# ELEKTRA-PMIC_v0_2-Half_frame_shield_for_.net
KiCad netlist of a schematic drawn in EAGLE
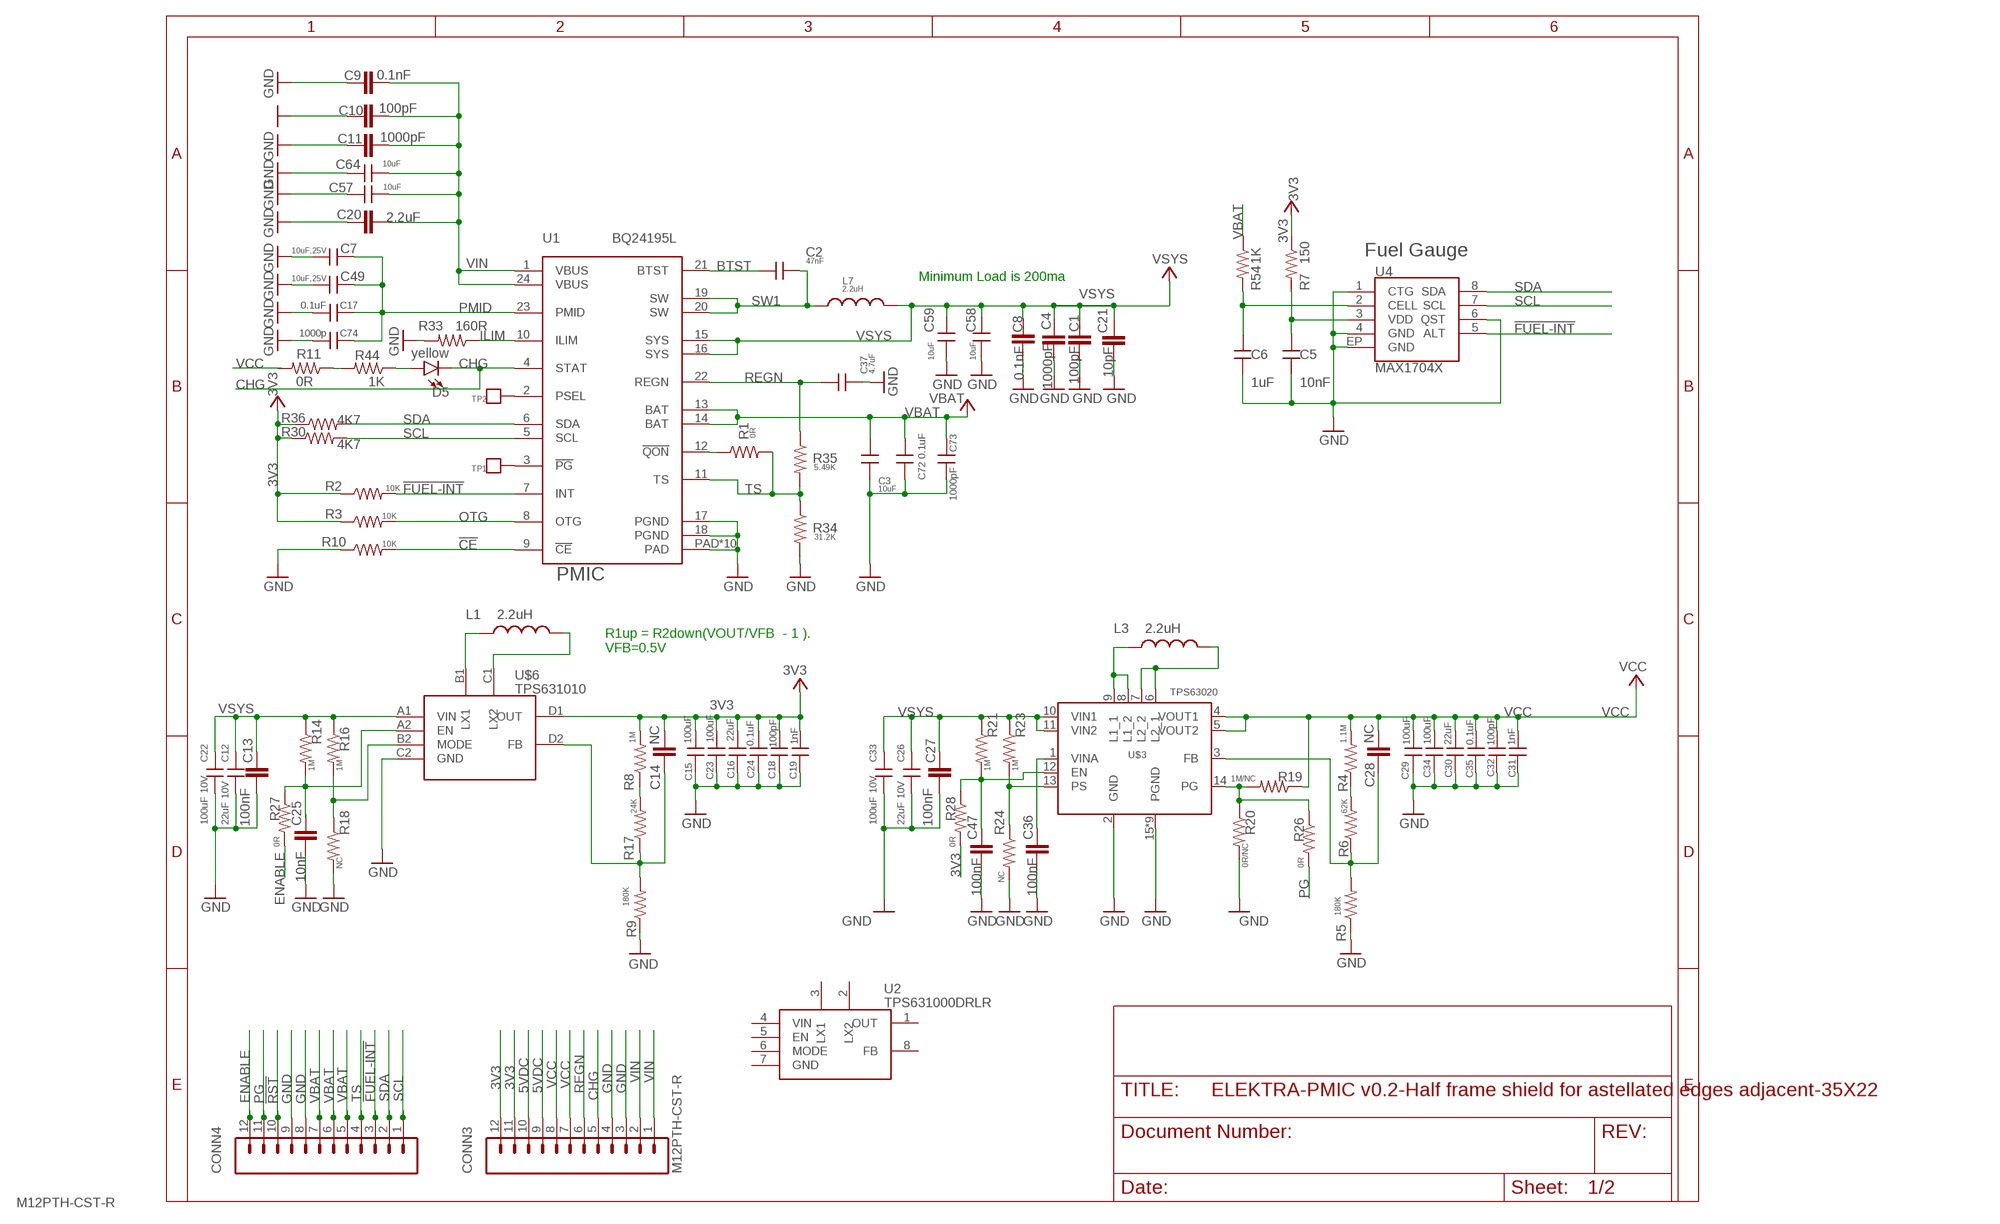
[diagram p0: schematic, sheet 1]

(export (version "E")
  (design (tool "Eeschema 10.0.6"))
  (components
    (comp (ref "C1")
      (value "100pF")
      (footprint "eagle-import:C0402_B")
      (libsource (lib "eagle-import") (part "CAP_1"))
    )
    (comp (ref "C2")
      (value "47nF")
      (footprint "eagle-import:C-0402")
      (libsource (lib "eagle-import") (part "particle SZ_CAP0402"))
    )
    (comp (ref "C3")
      (value "10uF")
      (footprint "eagle-import:C0603")
      (libsource (lib "eagle-import") (part "particle SZ_CAPC0603"))
    )
    (comp (ref "C4")
      (value "1000pF")
      (footprint "eagle-import:C0402_B")
      (libsource (lib "eagle-import") (part "CAP_1"))
    )
    (comp (ref "C5")
      (value "10nF")
      (footprint "eagle-import:C0402")
      (libsource (lib "eagle-import") (part "particle SZ_CAP0402A"))
    )
    (comp (ref "C6")
      (value "1uF")
      (footprint "eagle-import:C0402")
      (libsource (lib "eagle-import") (part "particle SZ_CAP0402A"))
    )
    (comp (ref "C7")
      (value "10uF,25V")
      (footprint "eagle-import:C-0603A")
      (libsource (lib "eagle-import") (part "particle SZ_CAP0603A"))
    )
    (comp (ref "C8")
      (value "0.1nF")
      (footprint "eagle-import:C0402_B")
      (libsource (lib "eagle-import") (part "CAP_1"))
    )
    (comp (ref "C9")
      (value "0.1nF")
      (footprint "eagle-import:C0402_B")
      (libsource (lib "eagle-import") (part "CAP_1"))
    )
    (comp (ref "C10")
      (value "100pF")
      (footprint "eagle-import:C0402_B")
      (libsource (lib "eagle-import") (part "CAP_1"))
    )
    (comp (ref "C11")
      (value "1000pF")
      (footprint "eagle-import:C0402_B")
      (libsource (lib "eagle-import") (part "CAP_1"))
    )
    (comp (ref "C12")
      (value "22uF 10V")
      (footprint "eagle-import:C0805")
      (libsource (lib "eagle-import") (part "particle SZ_21650216_CAPC0805"))
    )
    (comp (ref "C13")
      (value "100nF")
      (footprint "eagle-import:C0402_B")
      (libsource (lib "eagle-import") (part "CAP_1"))
    )
    (comp (ref "C14")
      (value "NC")
      (footprint "eagle-import:C0402_B")
      (libsource (lib "eagle-import") (part "CAP_1"))
    )
    (comp (ref "C15")
      (value "100uF")
      (footprint "eagle-import:C1206")
      (libsource (lib "eagle-import") (part "particle SZ_21650216_CAPC1206"))
    )
    (comp (ref "C16")
      (value "22uF")
      (footprint "eagle-import:C-0603A")
      (libsource (lib "eagle-import") (part "particle SZ_21650216_CAP0603A"))
    )
    (comp (ref "C17")
      (value "0.1uF")
      (footprint "eagle-import:C0402")
      (libsource (lib "eagle-import") (part "CAP0402A"))
    )
    (comp (ref "C18")
      (value "100pF")
      (footprint "eagle-import:C0402")
      (libsource (lib "eagle-import") (part "particle SZ_CAP0402A"))
    )
    (comp (ref "C19")
      (value "1nF")
      (footprint "eagle-import:C0402")
      (libsource (lib "eagle-import") (part "particle SZ_CAP0402A"))
    )
    (comp (ref "C20")
      (value "2.2uF")
      (footprint "eagle-import:C0402_B")
      (libsource (lib "eagle-import") (part "CAP_1"))
    )
    (comp (ref "C21")
      (value "10pF")
      (footprint "eagle-import:C0402_B")
      (libsource (lib "eagle-import") (part "CAP_1"))
    )
    (comp (ref "C22")
      (value "100uF 10V")
      (footprint "eagle-import:C1206")
      (libsource (lib "eagle-import") (part "particle SZ_21650216_CAPC1206"))
    )
    (comp (ref "C23")
      (value "100uF")
      (footprint "eagle-import:C1206")
      (libsource (lib "eagle-import") (part "particle SZ_21650216_CAPC1206"))
    )
    (comp (ref "C24")
      (value "0.1uF")
      (footprint "eagle-import:C0402")
      (libsource (lib "eagle-import") (part "particle SZ_CAP0402A"))
    )
    (comp (ref "C25")
      (value "10nF")
      (footprint "eagle-import:C0402_B")
      (libsource (lib "eagle-import") (part "CAP_1"))
    )
    (comp (ref "C26")
      (value "22uF 10V")
      (footprint "eagle-import:C0805")
      (libsource (lib "eagle-import") (part "particle SZ_21650216_CAPC0805"))
    )
    (comp (ref "C27")
      (value "100nF")
      (footprint "eagle-import:C0402_B")
      (libsource (lib "eagle-import") (part "CAP_1"))
    )
    (comp (ref "C28")
      (value "NC")
      (footprint "eagle-import:C0402_B")
      (libsource (lib "eagle-import") (part "CAP_1"))
    )
    (comp (ref "C29")
      (value "100uF")
      (footprint "eagle-import:C1206")
      (libsource (lib "eagle-import") (part "particle SZ_21650216_CAPC1206"))
    )
    (comp (ref "C30")
      (value "22uF")
      (footprint "eagle-import:C-0603A")
      (libsource (lib "eagle-import") (part "particle SZ_21650216_CAP0603A"))
    )
    (comp (ref "C31")
      (value "1nF")
      (footprint "eagle-import:C0402")
      (libsource (lib "eagle-import") (part "particle SZ_CAP0402A"))
    )
    (comp (ref "C32")
      (value "100pF")
      (footprint "eagle-import:C0402")
      (libsource (lib "eagle-import") (part "particle SZ_CAP0402A"))
    )
    (comp (ref "C33")
      (value "100uF 10V")
      (footprint "eagle-import:C1206")
      (libsource (lib "eagle-import") (part "particle SZ_21650216_CAPC1206"))
    )
    (comp (ref "C34")
      (value "100uF")
      (footprint "eagle-import:C1206")
      (libsource (lib "eagle-import") (part "particle SZ_21650216_CAPC1206"))
    )
    (comp (ref "C35")
      (value "0.1uF")
      (footprint "eagle-import:C0402")
      (libsource (lib "eagle-import") (part "particle SZ_CAP0402A"))
    )
    (comp (ref "C36")
      (value "100nF")
      (footprint "eagle-import:C0402_B")
      (libsource (lib "eagle-import") (part "CAP_1"))
    )
    (comp (ref "C37")
      (value "4.7uF")
      (footprint "eagle-import:C0402")
      (libsource (lib "eagle-import") (part "particle SZ_CAP0402A"))
    )
    (comp (ref "C47")
      (value "100nF")
      (footprint "eagle-import:C0402_B")
      (libsource (lib "eagle-import") (part "CAP_1"))
    )
    (comp (ref "C49")
      (value "10uF,25V")
      (footprint "eagle-import:C-0603A")
      (libsource (lib "eagle-import") (part "particle SZ_CAP0603A"))
    )
    (comp (ref "C57")
      (value "10uF")
      (footprint "eagle-import:C-0603A")
      (libsource (lib "eagle-import") (part "particle SZ_CAP0603A"))
    )
    (comp (ref "C58")
      (value "10uF")
      (footprint "eagle-import:C-0603A")
      (libsource (lib "eagle-import") (part "particle SZ_CAP0603A"))
    )
    (comp (ref "C59")
      (value "10uF")
      (footprint "eagle-import:C-0603A")
      (libsource (lib "eagle-import") (part "particle SZ_CAP0603A"))
    )
    (comp (ref "C64")
      (value "10uF")
      (footprint "eagle-import:C-0603A")
      (libsource (lib "eagle-import") (part "particle SZ_CAP0603A"))
    )
    (comp (ref "C72")
      (value "0.1uF")
      (footprint "eagle-import:C-0402")
      (libsource (lib "eagle-import") (part "particle SZ_CAP0402"))
    )
    (comp (ref "C73")
      (value "1000pF")
      (footprint "eagle-import:C-0402")
      (libsource (lib "eagle-import") (part "particle SZ_CAP0402"))
    )
    (comp (ref "C74")
      (value "1000p")
      (footprint "eagle-import:C-0402")
      (libsource (lib "eagle-import") (part "particle SZ_CAP0402"))
    )
    (comp (ref "CONN3")
      (value "M12PTH-CST-R")
      (footprint "eagle-import:1X12-CASTELLATED")
      (libsource (lib "eagle-import") (part "M12PTH-CST-R"))
    )
    (comp (ref "CONN4")
      (value "M12PTH-CST-R")
      (footprint "eagle-import:1X12-CASTELLATED")
      (libsource (lib "eagle-import") (part "M12PTH-CST-R"))
    )
    (comp (ref "D5")
      (value "yellow")
      (footprint "eagle-import:LED-0603")
      (libsource (lib "eagle-import") (part "LED-RED0603"))
    )
    (comp (ref "L1")
      (value "2.2uH")
      (footprint "eagle-import:INDUCTOR-VLS-E")
      (libsource (lib "eagle-import") (part "INDUCTOR-SPARKFUNVLS3012ET-4R7M"))
    )
    (comp (ref "L3")
      (value "2.2uH")
      (footprint "eagle-import:INDUCTOR-VLS-E")
      (libsource (lib "eagle-import") (part "INDUCTOR-SPARKFUNVLS3012ET-4R7M"))
    )
    (comp (ref "L7")
      (value "2.2uH")
      (footprint "eagle-import:INDUCTOR-4040")
      (libsource (lib "eagle-import") (part "INDUCTORI"))
    )
    (comp (ref "R1")
      (value "0R")
      (footprint "eagle-import:R0402_B")
      (libsource (lib "eagle-import") (part "Spark_R-US_"))
    )
    (comp (ref "R2")
      (value "10K")
      (footprint "eagle-import:R0402_B")
      (libsource (lib "eagle-import") (part "Spark_R-US_"))
    )
    (comp (ref "R3")
      (value "10K")
      (footprint "eagle-import:R0402_B")
      (libsource (lib "eagle-import") (part "Spark_R-US_"))
    )
    (comp (ref "R4")
      (value "1.1M")
      (footprint "eagle-import:R0402_B")
      (libsource (lib "eagle-import") (part "Spark_R-US_"))
    )
    (comp (ref "R5")
      (value "180K")
      (footprint "eagle-import:R0402_B")
      (libsource (lib "eagle-import") (part "Spark_R-US_"))
    )
    (comp (ref "R6")
      (value "62K")
      (footprint "eagle-import:R0402_B")
      (libsource (lib "eagle-import") (part "Spark_R-US_"))
    )
    (comp (ref "R7")
      (value "150")
      (footprint "eagle-import:R0402_B")
      (libsource (lib "eagle-import") (part "R-US_"))
    )
    (comp (ref "R8")
      (value "1M")
      (footprint "eagle-import:R0402_B")
      (libsource (lib "eagle-import") (part "Spark_R-US_"))
    )
    (comp (ref "R9")
      (value "180K")
      (footprint "eagle-import:R0402_B")
      (libsource (lib "eagle-import") (part "Spark_R-US_"))
    )
    (comp (ref "R10")
      (value "10K")
      (footprint "eagle-import:R0402_B")
      (libsource (lib "eagle-import") (part "Spark_R-US_"))
    )
    (comp (ref "R11")
      (value "0R")
      (footprint "eagle-import:R0402_B")
      (libsource (lib "eagle-import") (part "R-US_"))
    )
    (comp (ref "R14")
      (value "1M")
      (footprint "eagle-import:R0402_B")
      (libsource (lib "eagle-import") (part "Spark_R-US_"))
    )
    (comp (ref "R16")
      (value "1M")
      (footprint "eagle-import:R0402_B")
      (libsource (lib "eagle-import") (part "Spark_R-US_"))
    )
    (comp (ref "R17")
      (value "24K")
      (footprint "eagle-import:R0402_B")
      (libsource (lib "eagle-import") (part "Spark_R-US_"))
    )
    (comp (ref "R18")
      (value "NC")
      (footprint "eagle-import:R0402_B")
      (libsource (lib "eagle-import") (part "Spark_R-US_"))
    )
    (comp (ref "R19")
      (value "1M/NC")
      (footprint "eagle-import:R0402_B")
      (libsource (lib "eagle-import") (part "Spark_R-US_"))
    )
    (comp (ref "R20")
      (value "0R/NC")
      (footprint "eagle-import:R0402_B")
      (libsource (lib "eagle-import") (part "Spark_R-US_"))
    )
    (comp (ref "R21")
      (value "1M")
      (footprint "eagle-import:R0402_B")
      (libsource (lib "eagle-import") (part "Spark_R-US_"))
    )
    (comp (ref "R23")
      (value "1M")
      (footprint "eagle-import:R0402_B")
      (libsource (lib "eagle-import") (part "Spark_R-US_"))
    )
    (comp (ref "R24")
      (value "NC")
      (footprint "eagle-import:R0402_B")
      (libsource (lib "eagle-import") (part "Spark_R-US_"))
    )
    (comp (ref "R26")
      (value "0R")
      (footprint "eagle-import:R0402_B")
      (libsource (lib "eagle-import") (part "Spark_R-US_"))
    )
    (comp (ref "R27")
      (value "0R")
      (footprint "eagle-import:R0402_B")
      (libsource (lib "eagle-import") (part "Spark_R-US_"))
    )
    (comp (ref "R28")
      (value "0R")
      (footprint "eagle-import:R0402_B")
      (libsource (lib "eagle-import") (part "Spark_R-US_"))
    )
    (comp (ref "R30")
      (value "4K7")
      (footprint "eagle-import:R0402_B")
      (libsource (lib "eagle-import") (part "R-US_"))
    )
    (comp (ref "R33")
      (value "160R")
      (footprint "eagle-import:R0402_B")
      (libsource (lib "eagle-import") (part "R-US_"))
    )
    (comp (ref "R34")
      (value "31.2K")
      (footprint "eagle-import:R0402_B")
      (libsource (lib "eagle-import") (part "Spark_R-US_"))
    )
    (comp (ref "R35")
      (value "5.49K")
      (footprint "eagle-import:R0402_B")
      (libsource (lib "eagle-import") (part "Spark_R-US_"))
    )
    (comp (ref "R36")
      (value "4K7")
      (footprint "eagle-import:R0402_B")
      (libsource (lib "eagle-import") (part "R-US_"))
    )
    (comp (ref "R44")
      (value "1K")
      (footprint "eagle-import:R0402_B")
      (libsource (lib "eagle-import") (part "R-US_"))
    )
    (comp (ref "R54")
      (value "1K")
      (footprint "eagle-import:R0402_B")
      (libsource (lib "eagle-import") (part "R-US_"))
    )
    (comp (ref "TP1")
      (value "TP")
      (footprint "eagle-import:TP0.7MM")
      (libsource (lib "eagle-import") (part "TP"))
    )
    (comp (ref "TP2")
      (value "TP")
      (footprint "eagle-import:TP0.7MM")
      (libsource (lib "eagle-import") (part "TP"))
    )
    (comp (ref "U$3")
      (value "TPS63020")
      (footprint "eagle-import:TPS63020")
      (libsource (lib "eagle-import") (part "TPS63020"))
    )
    (comp (ref "U$6")
      (value "TPS631010")
      (footprint "eagle-import:DSBGA")
      (libsource (lib "eagle-import") (part "TPS631010"))
    )
    (comp (ref "U1")
      (value "BQ24195L")
      (footprint "eagle-import:QFN24")
      (libsource (lib "eagle-import") (part "BQ24298RTWR"))
    )
    (comp (ref "U2")
      (value "TPS631000DRLR")
      (footprint "eagle-import:SOT538")
      (libsource (lib "eagle-import") (part "TPS631000DRLR"))
    )
    (comp (ref "U4")
      (value "MAX1704X")
      (footprint "eagle-import:TDFN-8")
      (libsource (lib "eagle-import") (part "MAX1704X"))
    )
  )
  (nets
    (net (code "1") (name "3V3") (class "Default")
      (node (ref "C14") (pin "2") (pinfunction "P$2_2") (pintype "passive"))
      (node (ref "C15") (pin "1") (pinfunction "1_1") (pintype "bidirectional"))
      (node (ref "C16") (pin "1") (pinfunction "1_1") (pintype "bidirectional"))
      (node (ref "C18") (pin "1") (pinfunction "1_1") (pintype "bidirectional"))
      (node (ref "C19") (pin "1") (pinfunction "1_1") (pintype "bidirectional"))
      (node (ref "C23") (pin "1") (pinfunction "1_1") (pintype "bidirectional"))
      (node (ref "C24") (pin "1") (pinfunction "1_1") (pintype "bidirectional"))
      (node (ref "CONN3") (pin "11") (pinfunction "11_11") (pintype "passive"))
      (node (ref "CONN3") (pin "12") (pinfunction "12_12") (pintype "passive"))
      (node (ref "R2") (pin "1") (pinfunction "1_1") (pintype "passive"))
      (node (ref "R28") (pin "2") (pinfunction "2_2") (pintype "passive"))
      (node (ref "R3") (pin "1") (pinfunction "1_1") (pintype "passive"))
      (node (ref "R30") (pin "1") (pinfunction "1_1") (pintype "passive"))
      (node (ref "R36") (pin "1") (pinfunction "1_1") (pintype "passive"))
      (node (ref "R7") (pin "1") (pinfunction "1_1") (pintype "passive"))
      (node (ref "R8") (pin "2") (pinfunction "2_2") (pintype "passive"))
      (node (ref "U$6") (pin "D1") (pinfunction "OUT_D1") (pintype "bidirectional"))
    )
    (net (code "2") (name "5VDC") (class "Default")
      (node (ref "CONN3") (pin "10") (pinfunction "10_10") (pintype "passive"))
      (node (ref "CONN3") (pin "9") (pinfunction "9_9") (pintype "passive"))
    )
    (net (code "3") (name "BTST") (class "Default")
      (node (ref "C2") (pin "1") (pinfunction "1_1") (pintype "bidirectional"))
      (node (ref "U1") (pin "21") (pinfunction "BTST_21") (pintype "bidirectional"))
    )
    (net (code "4") (name "CHG") (class "Default")
      (node (ref "CONN3") (pin "5") (pinfunction "5_5") (pintype "passive"))
      (node (ref "D5") (pin "C") (pinfunction "C_C") (pintype "passive"))
      (node (ref "U1") (pin "4") (pinfunction "STAT_4") (pintype "bidirectional"))
    )
    (net (code "5") (name "ENABLE") (class "Default")
      (node (ref "CONN4") (pin "12") (pinfunction "12_12") (pintype "passive"))
      (node (ref "R27") (pin "2") (pinfunction "2_2") (pintype "passive"))
    )
    (net (code "6") (name "GND") (class "Default")
      (node (ref "C1") (pin "1") (pinfunction "P$1_1") (pintype "passive"))
      (node (ref "C10") (pin "1") (pinfunction "P$1_1") (pintype "passive"))
      (node (ref "C11") (pin "1") (pinfunction "P$1_1") (pintype "passive"))
      (node (ref "C12") (pin "2") (pinfunction "2_2") (pintype "bidirectional"))
      (node (ref "C13") (pin "1") (pinfunction "P$1_1") (pintype "passive"))
      (node (ref "C15") (pin "2") (pinfunction "2_2") (pintype "bidirectional"))
      (node (ref "C16") (pin "2") (pinfunction "2_2") (pintype "bidirectional"))
      (node (ref "C17") (pin "1") (pinfunction "1_1") (pintype "bidirectional"))
      (node (ref "C18") (pin "2") (pinfunction "2_2") (pintype "bidirectional"))
      (node (ref "C19") (pin "2") (pinfunction "2_2") (pintype "bidirectional"))
      (node (ref "C20") (pin "1") (pinfunction "P$1_1") (pintype "passive"))
      (node (ref "C21") (pin "1") (pinfunction "P$1_1") (pintype "passive"))
      (node (ref "C22") (pin "2") (pinfunction "2_2") (pintype "bidirectional"))
      (node (ref "C23") (pin "2") (pinfunction "2_2") (pintype "bidirectional"))
      (node (ref "C24") (pin "2") (pinfunction "2_2") (pintype "bidirectional"))
      (node (ref "C25") (pin "1") (pinfunction "P$1_1") (pintype "passive"))
      (node (ref "C26") (pin "2") (pinfunction "2_2") (pintype "bidirectional"))
      (node (ref "C27") (pin "1") (pinfunction "P$1_1") (pintype "passive"))
      (node (ref "C29") (pin "2") (pinfunction "2_2") (pintype "bidirectional"))
      (node (ref "C3") (pin "2") (pinfunction "2_2") (pintype "bidirectional"))
      (node (ref "C30") (pin "2") (pinfunction "2_2") (pintype "bidirectional"))
      (node (ref "C31") (pin "2") (pinfunction "2_2") (pintype "bidirectional"))
      (node (ref "C32") (pin "2") (pinfunction "2_2") (pintype "bidirectional"))
      (node (ref "C33") (pin "2") (pinfunction "2_2") (pintype "bidirectional"))
      (node (ref "C34") (pin "2") (pinfunction "2_2") (pintype "bidirectional"))
      (node (ref "C35") (pin "2") (pinfunction "2_2") (pintype "bidirectional"))
      (node (ref "C36") (pin "1") (pinfunction "P$1_1") (pintype "passive"))
      (node (ref "C37") (pin "2") (pinfunction "2_2") (pintype "bidirectional"))
      (node (ref "C4") (pin "1") (pinfunction "P$1_1") (pintype "passive"))
      (node (ref "C47") (pin "1") (pinfunction "P$1_1") (pintype "passive"))
      (node (ref "C49") (pin "2") (pinfunction "2_2") (pintype "bidirectional"))
      (node (ref "C5") (pin "2") (pinfunction "2_2") (pintype "bidirectional"))
      (node (ref "C57") (pin "2") (pinfunction "2_2") (pintype "bidirectional"))
      (node (ref "C58") (pin "2") (pinfunction "2_2") (pintype "bidirectional"))
      (node (ref "C59") (pin "2") (pinfunction "2_2") (pintype "bidirectional"))
      (node (ref "C6") (pin "2") (pinfunction "2_2") (pintype "bidirectional"))
      (node (ref "C64") (pin "2") (pinfunction "2_2") (pintype "bidirectional"))
      (node (ref "C7") (pin "2") (pinfunction "2_2") (pintype "bidirectional"))
      (node (ref "C72") (pin "2") (pinfunction "2_2") (pintype "bidirectional"))
      (node (ref "C73") (pin "2") (pinfunction "2_2") (pintype "bidirectional"))
      (node (ref "C74") (pin "1") (pinfunction "1_1") (pintype "bidirectional"))
      (node (ref "C8") (pin "1") (pinfunction "P$1_1") (pintype "passive"))
      (node (ref "C9") (pin "1") (pinfunction "P$1_1") (pintype "passive"))
      (node (ref "CONN3") (pin "3") (pinfunction "3_3") (pintype "passive"))
      (node (ref "CONN3") (pin "4") (pinfunction "4_4") (pintype "passive"))
      (node (ref "CONN4") (pin "8") (pinfunction "8_8") (pintype "passive"))
      (node (ref "CONN4") (pin "9") (pinfunction "9_9") (pintype "passive"))
      (node (ref "R10") (pin "1") (pinfunction "1_1") (pintype "passive"))
      (node (ref "R18") (pin "2") (pinfunction "2_2") (pintype "passive"))
      (node (ref "R20") (pin "2") (pinfunction "2_2") (pintype "passive"))
      (node (ref "R24") (pin "2") (pinfunction "2_2") (pintype "passive"))
      (node (ref "R33") (pin "2") (pinfunction "2_2") (pintype "passive"))
      (node (ref "R34") (pin "2") (pinfunction "2_2") (pintype "passive"))
      (node (ref "R5") (pin "1") (pinfunction "1_1") (pintype "passive"))
      (node (ref "R9") (pin "1") (pinfunction "1_1") (pintype "passive"))
      (node (ref "U$3") (pin "15") (pinfunction "PGND_15") (pintype "bidirectional"))
      (node (ref "U$3") (pin "16") (pinfunction "PGND_16") (pintype "bidirectional"))
      (node (ref "U$3") (pin "17") (pinfunction "PGND_17") (pintype "bidirectional"))
      (node (ref "U$3") (pin "18") (pinfunction "PGND_18") (pintype "bidirectional"))
      (node (ref "U$3") (pin "19") (pinfunction "PGND_19") (pintype "bidirectional"))
      (node (ref "U$3") (pin "2") (pinfunction "GND_2") (pintype "bidirectional"))
      (node (ref "U$3") (pin "20") (pinfunction "PGND_20") (pintype "bidirectional"))
      (node (ref "U$3") (pin "21") (pinfunction "PGND_21") (pintype "bidirectional"))
      (node (ref "U$3") (pin "22") (pinfunction "PGND_22") (pintype "bidirectional"))
      (node (ref "U$3") (pin "23") (pinfunction "PGND_23") (pintype "bidirectional"))
      (node (ref "U$6") (pin "C2") (pinfunction "GND_C2") (pintype "bidirectional"))
      (node (ref "U1") (pin "17") (pinfunction "PGND_17") (pintype "passive"))
      (node (ref "U1") (pin "18") (pinfunction "PGND_18") (pintype "passive"))
      (node (ref "U1") (pin "PAD") (pinfunction "PAD_PAD") (pintype "power_in"))
      (node (ref "U1") (pin "PAD@1") (pinfunction "PAD_PAD@1") (pintype "power_in"))
      (node (ref "U1") (pin "PAD@2") (pinfunction "PAD_PAD@2") (pintype "power_in"))
      (node (ref "U1") (pin "PAD@3") (pinfunction "PAD_PAD@3") (pintype "power_in"))
      (node (ref "U1") (pin "PAD@4") (pinfunction "PAD_PAD@4") (pintype "power_in"))
      (node (ref "U1") (pin "PAD@5") (pinfunction "PAD_PAD@5") (pintype "power_in"))
      (node (ref "U1") (pin "PAD@6") (pinfunction "PAD_PAD@6") (pintype "power_in"))
      (node (ref "U1") (pin "PAD@7") (pinfunction "PAD_PAD@7") (pintype "power_in"))
      (node (ref "U1") (pin "PAD@8") (pinfunction "PAD_PAD@8") (pintype "power_in"))
      (node (ref "U1") (pin "PAD@9") (pinfunction "PAD_PAD@9") (pintype "power_in"))
      (node (ref "U4") (pin "1") (pinfunction "CTG_1") (pintype "bidirectional"))
      (node (ref "U4") (pin "4") (pinfunction "GND_4") (pintype "bidirectional"))
      (node (ref "U4") (pin "6") (pinfunction "QST_6") (pintype "bidirectional"))
      (node (ref "U4") (pin "EP") (pinfunction "GND_EP") (pintype "bidirectional"))
    )
    (net (code "7") (name "ILIM") (class "Default")
      (node (ref "R33") (pin "1") (pinfunction "1_1") (pintype "passive"))
      (node (ref "U1") (pin "10") (pinfunction "ILIM_10") (pintype "output"))
    )
    (net (code "8") (name "Net-(C14-P$1)") (class "Default")
      (node (ref "C14") (pin "1") (pinfunction "P$1_1") (pintype "passive"))
      (node (ref "R17") (pin "1") (pinfunction "1_1") (pintype "passive"))
      (node (ref "R9") (pin "2") (pinfunction "2_2") (pintype "passive"))
      (node (ref "U$6") (pin "D2") (pinfunction "FB_D2") (pintype "bidirectional"))
    )
    (net (code "9") (name "Net-(C25-P$2)") (class "Default")
      (node (ref "C25") (pin "2") (pinfunction "P$2_2") (pintype "passive"))
      (node (ref "R14") (pin "2") (pinfunction "2_2") (pintype "passive"))
      (node (ref "R27") (pin "1") (pinfunction "1_1") (pintype "passive"))
      (node (ref "U$6") (pin "A2") (pinfunction "EN_A2") (pintype "bidirectional"))
    )
    (net (code "10") (name "Net-(C28-P$1)") (class "Default")
      (node (ref "C28") (pin "1") (pinfunction "P$1_1") (pintype "passive"))
      (node (ref "R5") (pin "2") (pinfunction "2_2") (pintype "passive"))
      (node (ref "R6") (pin "1") (pinfunction "1_1") (pintype "passive"))
      (node (ref "U$3") (pin "3") (pinfunction "FB_3") (pintype "bidirectional"))
    )
    (net (code "11") (name "Net-(C36-P$2)") (class "Default")
      (node (ref "C36") (pin "2") (pinfunction "P$2_2") (pintype "passive"))
      (node (ref "U$3") (pin "1") (pinfunction "VINA_1") (pintype "bidirectional"))
    )
    (net (code "12") (name "Net-(C47-P$2)") (class "Default")
      (node (ref "C47") (pin "2") (pinfunction "P$2_2") (pintype "passive"))
      (node (ref "R21") (pin "2") (pinfunction "2_2") (pintype "passive"))
      (node (ref "R28") (pin "1") (pinfunction "1_1") (pintype "passive"))
      (node (ref "U$3") (pin "12") (pinfunction "EN_12") (pintype "bidirectional"))
    )
    (net (code "13") (name "Net-(D5-PadA)") (class "Default")
      (node (ref "D5") (pin "A") (pinfunction "A_A") (pintype "passive"))
      (node (ref "R44") (pin "1") (pinfunction "1_1") (pintype "passive"))
    )
    (net (code "14") (name "Net-(L1-1)") (class "Default")
      (node (ref "L1") (pin "P$1") (pinfunction "1_P$1") (pintype "passive"))
      (node (ref "U$6") (pin "B1") (pinfunction "LX1_B1") (pintype "bidirectional"))
    )
    (net (code "15") (name "Net-(L1-2)") (class "Default")
      (node (ref "L1") (pin "P$2") (pinfunction "2_P$2") (pintype "passive"))
      (node (ref "U$6") (pin "C1") (pinfunction "LX2_C1") (pintype "bidirectional"))
    )
    (net (code "16") (name "Net-(L3-1)") (class "Default")
      (node (ref "L3") (pin "P$1") (pinfunction "1_P$1") (pintype "passive"))
      (node (ref "U$3") (pin "8") (pinfunction "L1_2_8") (pintype "bidirectional"))
      (node (ref "U$3") (pin "9") (pinfunction "L1_1_9") (pintype "bidirectional"))
    )
    (net (code "17") (name "Net-(L3-2)") (class "Default")
      (node (ref "L3") (pin "P$2") (pinfunction "2_P$2") (pintype "passive"))
      (node (ref "U$3") (pin "6") (pinfunction "L2_1_6") (pintype "bidirectional"))
      (node (ref "U$3") (pin "7") (pinfunction "L2_2_7") (pintype "bidirectional"))
    )
    (net (code "18") (name "Net-(R4-Pad1)") (class "Default")
      (node (ref "R4") (pin "1") (pinfunction "1_1") (pintype "passive"))
      (node (ref "R6") (pin "2") (pinfunction "2_2") (pintype "passive"))
    )
    (net (code "19") (name "Net-(R11-Pad1)") (class "Default")
      (node (ref "R11") (pin "1") (pinfunction "1_1") (pintype "passive"))
      (node (ref "R44") (pin "2") (pinfunction "2_2") (pintype "passive"))
    )
    (net (code "20") (name "Net-(R17-Pad2)") (class "Default")
      (node (ref "R17") (pin "2") (pinfunction "2_2") (pintype "passive"))
      (node (ref "R8") (pin "1") (pinfunction "1_1") (pintype "passive"))
    )
    (net (code "21") (name "Net-(TP1-1)") (class "Default")
      (node (ref "TP1") (pin "P$1") (pinfunction "1_P$1") (pintype "bidirectional"))
      (node (ref "U1") (pin "3") (pinfunction "~{PG}_3") (pintype "output"))
    )
    (net (code "22") (name "Net-(TP2-1)") (class "Default")
      (node (ref "TP2") (pin "P$1") (pinfunction "1_P$1") (pintype "bidirectional"))
      (node (ref "U1") (pin "2") (pinfunction "PSEL_2") (pintype "output"))
    )
    (net (code "23") (name "Net-(U$3-PG)") (class "Default")
      (node (ref "R19") (pin "2") (pinfunction "2_2") (pintype "passive"))
      (node (ref "R20") (pin "1") (pinfunction "1_1") (pintype "passive"))
      (node (ref "R26") (pin "1") (pinfunction "1_1") (pintype "passive"))
      (node (ref "U$3") (pin "14") (pinfunction "PG_14") (pintype "bidirectional"))
    )
    (net (code "24") (name "Net-(U$3-PS)") (class "Default")
      (node (ref "R23") (pin "2") (pinfunction "2_2") (pintype "passive"))
      (node (ref "R24") (pin "1") (pinfunction "1_1") (pintype "passive"))
      (node (ref "U$3") (pin "13") (pinfunction "PS_13") (pintype "bidirectional"))
    )
    (net (code "25") (name "Net-(U$6-MODE)") (class "Default")
      (node (ref "R16") (pin "2") (pinfunction "2_2") (pintype "passive"))
      (node (ref "R18") (pin "1") (pinfunction "1_1") (pintype "passive"))
      (node (ref "U$6") (pin "B2") (pinfunction "MODE_B2") (pintype "bidirectional"))
    )
    (net (code "26") (name "Net-(U1-~{QON})") (class "Default")
      (node (ref "R1") (pin "1") (pinfunction "1_1") (pintype "passive"))
      (node (ref "U1") (pin "12") (pinfunction "~{QON}_12") (pintype "bidirectional"))
    )
    (net (code "27") (name "Net-(U4-CELL)") (class "Default")
      (node (ref "C6") (pin "1") (pinfunction "1_1") (pintype "bidirectional"))
      (node (ref "R54") (pin "2") (pinfunction "2_2") (pintype "passive"))
      (node (ref "U4") (pin "2") (pinfunction "CELL_2") (pintype "bidirectional"))
    )
    (net (code "28") (name "Net-(U4-VDD)") (class "Default")
      (node (ref "C5") (pin "1") (pinfunction "1_1") (pintype "bidirectional"))
      (node (ref "R7") (pin "2") (pinfunction "2_2") (pintype "passive"))
      (node (ref "U4") (pin "3") (pinfunction "VDD_3") (pintype "bidirectional"))
    )
    (net (code "29") (name "OTG") (class "Default")
      (node (ref "R3") (pin "2") (pinfunction "2_2") (pintype "passive"))
      (node (ref "U1") (pin "8") (pinfunction "OTG_8") (pintype "bidirectional"))
    )
    (net (code "30") (name "PG") (class "Default")
      (node (ref "CONN4") (pin "11") (pinfunction "11_11") (pintype "passive"))
      (node (ref "R26") (pin "2") (pinfunction "2_2") (pintype "passive"))
    )
    (net (code "31") (name "PMID") (class "Default")
      (node (ref "C17") (pin "2") (pinfunction "2_2") (pintype "bidirectional"))
      (node (ref "C49") (pin "1") (pinfunction "1_1") (pintype "bidirectional"))
      (node (ref "C7") (pin "1") (pinfunction "1_1") (pintype "bidirectional"))
      (node (ref "C74") (pin "2") (pinfunction "2_2") (pintype "bidirectional"))
      (node (ref "U1") (pin "23") (pinfunction "PMID_23") (pintype "passive"))
    )
    (net (code "32") (name "REGN") (class "Default")
      (node (ref "C37") (pin "1") (pinfunction "1_1") (pintype "bidirectional"))
      (node (ref "CONN3") (pin "6") (pinfunction "6_6") (pintype "passive"))
      (node (ref "R35") (pin "1") (pinfunction "1_1") (pintype "passive"))
      (node (ref "U1") (pin "22") (pinfunction "REGN_22") (pintype "bidirectional"))
    )
    (net (code "33") (name "SCL") (class "Default")
      (node (ref "CONN4") (pin "1") (pinfunction "1_1") (pintype "passive"))
      (node (ref "R30") (pin "2") (pinfunction "2_2") (pintype "passive"))
      (node (ref "U1") (pin "5") (pinfunction "SCL_5") (pintype "output"))
      (node (ref "U4") (pin "7") (pinfunction "SCL_7") (pintype "bidirectional"))
    )
    (net (code "34") (name "SDA") (class "Default")
      (node (ref "CONN4") (pin "2") (pinfunction "2_2") (pintype "passive"))
      (node (ref "R36") (pin "2") (pinfunction "2_2") (pintype "passive"))
      (node (ref "U1") (pin "6") (pinfunction "SDA_6") (pintype "bidirectional"))
      (node (ref "U4") (pin "8") (pinfunction "SDA_8") (pintype "bidirectional"))
    )
    (net (code "35") (name "SW1") (class "Default")
      (node (ref "C2") (pin "2") (pinfunction "2_2") (pintype "bidirectional"))
      (node (ref "L7") (pin "P$1") (pinfunction "1_P$1") (pintype "passive"))
      (node (ref "U1") (pin "19") (pinfunction "SW_19") (pintype "power_in"))
      (node (ref "U1") (pin "20") (pinfunction "SW_20") (pintype "power_in"))
    )
    (net (code "36") (name "TS") (class "Default")
      (node (ref "CONN4") (pin "4") (pinfunction "4_4") (pintype "passive"))
      (node (ref "R1") (pin "2") (pinfunction "2_2") (pintype "passive"))
      (node (ref "R34") (pin "1") (pinfunction "1_1") (pintype "passive"))
      (node (ref "R35") (pin "2") (pinfunction "2_2") (pintype "passive"))
      (node (ref "U1") (pin "11") (pinfunction "TS_11") (pintype "bidirectional"))
    )
    (net (code "37") (name "VBAT") (class "Default")
      (node (ref "C3") (pin "1") (pinfunction "1_1") (pintype "bidirectional"))
      (node (ref "C72") (pin "1") (pinfunction "1_1") (pintype "bidirectional"))
      (node (ref "C73") (pin "1") (pinfunction "1_1") (pintype "bidirectional"))
      (node (ref "CONN4") (pin "5") (pinfunction "5_5") (pintype "passive"))
      (node (ref "CONN4") (pin "6") (pinfunction "6_6") (pintype "passive"))
      (node (ref "CONN4") (pin "7") (pinfunction "7_7") (pintype "passive"))
      (node (ref "R54") (pin "1") (pinfunction "1_1") (pintype "passive"))
      (node (ref "U1") (pin "13") (pinfunction "BAT_13") (pintype "passive"))
      (node (ref "U1") (pin "14") (pinfunction "BAT_14") (pintype "power_in"))
    )
    (net (code "38") (name "VCC") (class "Default")
      (node (ref "C28") (pin "2") (pinfunction "P$2_2") (pintype "passive"))
      (node (ref "C29") (pin "1") (pinfunction "1_1") (pintype "bidirectional"))
      (node (ref "C30") (pin "1") (pinfunction "1_1") (pintype "bidirectional"))
      (node (ref "C31") (pin "1") (pinfunction "1_1") (pintype "bidirectional"))
      (node (ref "C32") (pin "1") (pinfunction "1_1") (pintype "bidirectional"))
      (node (ref "C34") (pin "1") (pinfunction "1_1") (pintype "bidirectional"))
      (node (ref "C35") (pin "1") (pinfunction "1_1") (pintype "bidirectional"))
      (node (ref "CONN3") (pin "7") (pinfunction "7_7") (pintype "passive"))
      (node (ref "CONN3") (pin "8") (pinfunction "8_8") (pintype "passive"))
      (node (ref "R11") (pin "2") (pinfunction "2_2") (pintype "passive"))
      (node (ref "R19") (pin "1") (pinfunction "1_1") (pintype "passive"))
      (node (ref "R4") (pin "2") (pinfunction "2_2") (pintype "passive"))
      (node (ref "U$3") (pin "4") (pinfunction "VOUT1_4") (pintype "bidirectional"))
      (node (ref "U$3") (pin "5") (pinfunction "VOUT2_5") (pintype "bidirectional"))
    )
    (net (code "39") (name "VIN") (class "Default")
      (node (ref "C10") (pin "2") (pinfunction "P$2_2") (pintype "passive"))
      (node (ref "C11") (pin "2") (pinfunction "P$2_2") (pintype "passive"))
      (node (ref "C20") (pin "2") (pinfunction "P$2_2") (pintype "passive"))
      (node (ref "C57") (pin "1") (pinfunction "1_1") (pintype "bidirectional"))
      (node (ref "C64") (pin "1") (pinfunction "1_1") (pintype "bidirectional"))
      (node (ref "C9") (pin "2") (pinfunction "P$2_2") (pintype "passive"))
      (node (ref "CONN3") (pin "1") (pinfunction "1_1") (pintype "passive"))
      (node (ref "CONN3") (pin "2") (pinfunction "2_2") (pintype "passive"))
      (node (ref "U1") (pin "1") (pinfunction "VBUS_1") (pintype "power_in"))
      (node (ref "U1") (pin "24") (pinfunction "VBUS_24") (pintype "passive"))
    )
    (net (code "40") (name "VSYS") (class "Default")
      (node (ref "C1") (pin "2") (pinfunction "P$2_2") (pintype "passive"))
      (node (ref "C12") (pin "1") (pinfunction "1_1") (pintype "bidirectional"))
      (node (ref "C13") (pin "2") (pinfunction "P$2_2") (pintype "passive"))
      (node (ref "C21") (pin "2") (pinfunction "P$2_2") (pintype "passive"))
      (node (ref "C22") (pin "1") (pinfunction "1_1") (pintype "bidirectional"))
      (node (ref "C26") (pin "1") (pinfunction "1_1") (pintype "bidirectional"))
      (node (ref "C27") (pin "2") (pinfunction "P$2_2") (pintype "passive"))
      (node (ref "C33") (pin "1") (pinfunction "1_1") (pintype "bidirectional"))
      (node (ref "C4") (pin "2") (pinfunction "P$2_2") (pintype "passive"))
      (node (ref "C58") (pin "1") (pinfunction "1_1") (pintype "bidirectional"))
      (node (ref "C59") (pin "1") (pinfunction "1_1") (pintype "bidirectional"))
      (node (ref "C8") (pin "2") (pinfunction "P$2_2") (pintype "passive"))
      (node (ref "L7") (pin "P$2") (pinfunction "2_P$2") (pintype "passive"))
      (node (ref "R14") (pin "1") (pinfunction "1_1") (pintype "passive"))
      (node (ref "R16") (pin "1") (pinfunction "1_1") (pintype "passive"))
      (node (ref "R21") (pin "1") (pinfunction "1_1") (pintype "passive"))
      (node (ref "R23") (pin "1") (pinfunction "1_1") (pintype "passive"))
      (node (ref "U$3") (pin "10") (pinfunction "VIN1_10") (pintype "bidirectional"))
      (node (ref "U$3") (pin "11") (pinfunction "VIN2_11") (pintype "bidirectional"))
      (node (ref "U$6") (pin "A1") (pinfunction "VIN_A1") (pintype "bidirectional"))
      (node (ref "U1") (pin "15") (pinfunction "SYS_15") (pintype "power_in"))
      (node (ref "U1") (pin "16") (pinfunction "SYS_16") (pintype "power_in"))
    )
    (net (code "41") (name "unconnected-(U2-EN-Pad5)") (class "Default")
      (node (ref "U2") (pin "5") (pinfunction "EN_5") (pintype "bidirectional"))
    )
    (net (code "42") (name "unconnected-(U2-FB-Pad8)") (class "Default")
      (node (ref "U2") (pin "8") (pinfunction "FB_8") (pintype "bidirectional"))
    )
    (net (code "43") (name "unconnected-(U2-GND-Pad7)") (class "Default")
      (node (ref "U2") (pin "7") (pinfunction "GND_7") (pintype "bidirectional"))
    )
    (net (code "44") (name "unconnected-(U2-LX1-Pad3)") (class "Default")
      (node (ref "U2") (pin "3") (pinfunction "LX1_3") (pintype "bidirectional"))
    )
    (net (code "45") (name "unconnected-(U2-LX2-Pad2)") (class "Default")
      (node (ref "U2") (pin "2") (pinfunction "LX2_2") (pintype "bidirectional"))
    )
    (net (code "46") (name "unconnected-(U2-MODE-Pad6)") (class "Default")
      (node (ref "U2") (pin "6") (pinfunction "MODE_6") (pintype "bidirectional"))
    )
    (net (code "47") (name "unconnected-(U2-OUT-Pad1)") (class "Default")
      (node (ref "U2") (pin "1") (pinfunction "OUT_1") (pintype "bidirectional"))
    )
    (net (code "48") (name "unconnected-(U2-VIN-Pad4)") (class "Default")
      (node (ref "U2") (pin "4") (pinfunction "VIN_4") (pintype "bidirectional"))
    )
    (net (code "49") (name "~{CE}") (class "Default")
      (node (ref "R10") (pin "2") (pinfunction "2_2") (pintype "passive"))
      (node (ref "U1") (pin "9") (pinfunction "~{CE}_9") (pintype "output"))
    )
    (net (code "50") (name "~{FUEL-INT}") (class "Default")
      (node (ref "CONN4") (pin "3") (pinfunction "3_3") (pintype "passive"))
      (node (ref "R2") (pin "2") (pinfunction "2_2") (pintype "passive"))
      (node (ref "U1") (pin "7") (pinfunction "INT_7") (pintype "bidirectional"))
      (node (ref "U4") (pin "5") (pinfunction "ALT_5") (pintype "bidirectional"))
    )
    (net (code "51") (name "~{RST}") (class "Default")
      (node (ref "CONN4") (pin "10") (pinfunction "10_10") (pintype "passive"))
    )
  )
)
